# Sparki_Senseboard.net
KiCad netlist of a schematic drawn in EAGLE
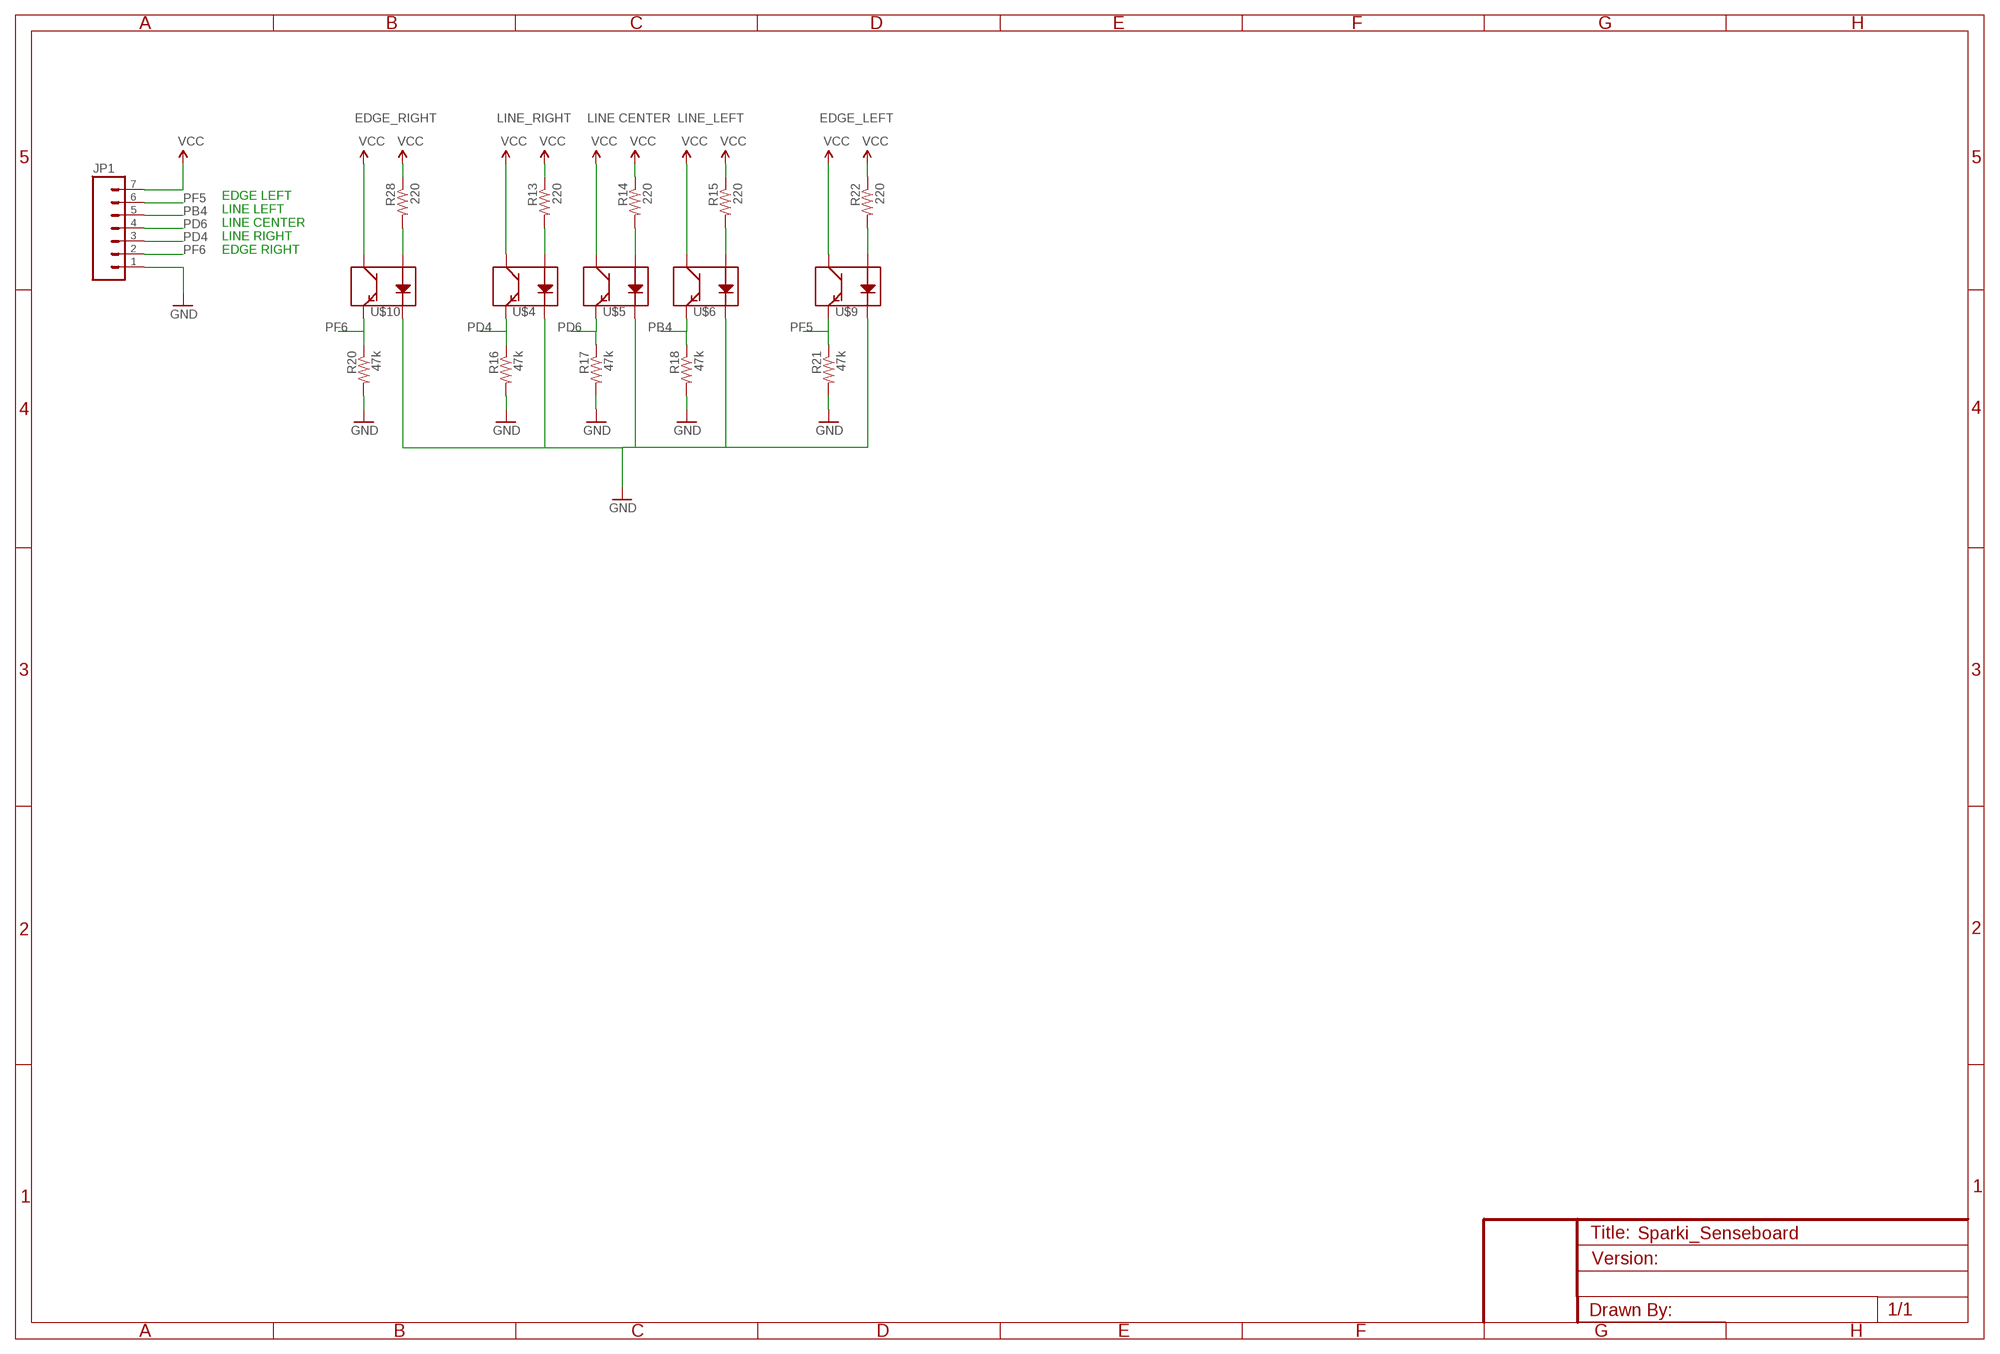
[diagram p0: schematic, sheet 1]

(export (version "E")
  (design (tool "Eeschema 10.0.6"))
  (components
    (comp (ref "JP1")
      (value "M07")
      (footprint "eagle-import:1X07")
      (libsource (lib "eagle-import") (part "M07"))
    )
    (comp (ref "R13")
      (value "220")
      (footprint "eagle-import:0603-RES")
      (libsource (lib "eagle-import") (part "RESISTOR0603-RES"))
    )
    (comp (ref "R14")
      (value "220")
      (footprint "eagle-import:0603-RES")
      (libsource (lib "eagle-import") (part "RESISTOR0603-RES"))
    )
    (comp (ref "R15")
      (value "220")
      (footprint "eagle-import:0603-RES")
      (libsource (lib "eagle-import") (part "RESISTOR0603-RES"))
    )
    (comp (ref "R16")
      (value "47k")
      (footprint "eagle-import:0603-RES")
      (libsource (lib "eagle-import") (part "RESISTOR0603-RES"))
    )
    (comp (ref "R17")
      (value "47k")
      (footprint "eagle-import:0603-RES")
      (libsource (lib "eagle-import") (part "RESISTOR0603-RES"))
    )
    (comp (ref "R18")
      (value "47k")
      (footprint "eagle-import:0603-RES")
      (libsource (lib "eagle-import") (part "RESISTOR0603-RES"))
    )
    (comp (ref "R20")
      (value "47k")
      (footprint "eagle-import:0603-RES")
      (libsource (lib "eagle-import") (part "RESISTOR0603-RES"))
    )
    (comp (ref "R21")
      (value "47k")
      (footprint "eagle-import:0603-RES")
      (libsource (lib "eagle-import") (part "RESISTOR0603-RES"))
    )
    (comp (ref "R22")
      (value "220")
      (footprint "eagle-import:0603-RES")
      (libsource (lib "eagle-import") (part "RESISTOR0603-RES"))
    )
    (comp (ref "R28")
      (value "220")
      (footprint "eagle-import:0603-RES")
      (libsource (lib "eagle-import") (part "RESISTOR0603-RES"))
    )
    (comp (ref "U$4")
      (value "LINE_RIGHT")
      (footprint "eagle-import:QRE1113")
      (libsource (lib "eagle-import") (part "QRE1113"))
    )
    (comp (ref "U$5")
      (value "LINE CENTER")
      (footprint "eagle-import:QRE1113")
      (libsource (lib "eagle-import") (part "QRE1113"))
    )
    (comp (ref "U$6")
      (value "LINE_LEFT")
      (footprint "eagle-import:QRE1113")
      (libsource (lib "eagle-import") (part "QRE1113"))
    )
    (comp (ref "U$9")
      (value "EDGE_LEFT")
      (footprint "eagle-import:QRE1113")
      (libsource (lib "eagle-import") (part "QRE1113"))
    )
    (comp (ref "U$10")
      (value "EDGE_RIGHT")
      (footprint "eagle-import:QRE1113")
      (libsource (lib "eagle-import") (part "QRE1113"))
    )
  )
  (nets
    (net (code "1") (name "/PB4") (class "Default")
      (node (ref "JP1") (pin "5") (pinfunction "5_5") (pintype "passive"))
      (node (ref "R18") (pin "1") (pinfunction "1_1") (pintype "passive"))
      (node (ref "U$6") (pin "4") (pinfunction "E_4") (pintype "bidirectional"))
    )
    (net (code "2") (name "/PD4") (class "Default")
      (node (ref "JP1") (pin "3") (pinfunction "3_3") (pintype "passive"))
      (node (ref "R16") (pin "1") (pinfunction "1_1") (pintype "passive"))
      (node (ref "U$4") (pin "4") (pinfunction "E_4") (pintype "bidirectional"))
    )
    (net (code "3") (name "/PD6") (class "Default")
      (node (ref "JP1") (pin "4") (pinfunction "4_4") (pintype "passive"))
      (node (ref "R17") (pin "1") (pinfunction "1_1") (pintype "passive"))
      (node (ref "U$5") (pin "4") (pinfunction "E_4") (pintype "bidirectional"))
    )
    (net (code "4") (name "/PF5") (class "Default")
      (node (ref "JP1") (pin "6") (pinfunction "6_6") (pintype "passive"))
      (node (ref "R21") (pin "1") (pinfunction "1_1") (pintype "passive"))
      (node (ref "U$9") (pin "4") (pinfunction "E_4") (pintype "bidirectional"))
    )
    (net (code "5") (name "/PF6") (class "Default")
      (node (ref "JP1") (pin "2") (pinfunction "2_2") (pintype "passive"))
      (node (ref "R20") (pin "1") (pinfunction "1_1") (pintype "passive"))
      (node (ref "U$10") (pin "4") (pinfunction "E_4") (pintype "bidirectional"))
    )
    (net (code "6") (name "GND") (class "Default")
      (node (ref "JP1") (pin "1") (pinfunction "1_1") (pintype "passive"))
      (node (ref "R16") (pin "2") (pinfunction "2_2") (pintype "passive"))
      (node (ref "R17") (pin "2") (pinfunction "2_2") (pintype "passive"))
      (node (ref "R18") (pin "2") (pinfunction "2_2") (pintype "passive"))
      (node (ref "R20") (pin "2") (pinfunction "2_2") (pintype "passive"))
      (node (ref "R21") (pin "2") (pinfunction "2_2") (pintype "passive"))
      (node (ref "U$10") (pin "2") (pinfunction "K_2") (pintype "bidirectional"))
      (node (ref "U$4") (pin "2") (pinfunction "K_2") (pintype "bidirectional"))
      (node (ref "U$5") (pin "2") (pinfunction "K_2") (pintype "bidirectional"))
      (node (ref "U$6") (pin "2") (pinfunction "K_2") (pintype "bidirectional"))
      (node (ref "U$9") (pin "2") (pinfunction "K_2") (pintype "bidirectional"))
    )
    (net (code "7") (name "Net-(U$4-A)") (class "Default")
      (node (ref "R13") (pin "2") (pinfunction "2_2") (pintype "passive"))
      (node (ref "U$4") (pin "1") (pinfunction "A_1") (pintype "bidirectional"))
    )
    (net (code "8") (name "Net-(U$5-A)") (class "Default")
      (node (ref "R14") (pin "2") (pinfunction "2_2") (pintype "passive"))
      (node (ref "U$5") (pin "1") (pinfunction "A_1") (pintype "bidirectional"))
    )
    (net (code "9") (name "Net-(U$6-A)") (class "Default")
      (node (ref "R15") (pin "2") (pinfunction "2_2") (pintype "passive"))
      (node (ref "U$6") (pin "1") (pinfunction "A_1") (pintype "bidirectional"))
    )
    (net (code "10") (name "Net-(U$9-A)") (class "Default")
      (node (ref "R22") (pin "2") (pinfunction "2_2") (pintype "passive"))
      (node (ref "U$9") (pin "1") (pinfunction "A_1") (pintype "bidirectional"))
    )
    (net (code "11") (name "Net-(U$10-A)") (class "Default")
      (node (ref "R28") (pin "2") (pinfunction "2_2") (pintype "passive"))
      (node (ref "U$10") (pin "1") (pinfunction "A_1") (pintype "bidirectional"))
    )
    (net (code "12") (name "VCC") (class "Default")
      (node (ref "JP1") (pin "7") (pinfunction "7_7") (pintype "passive"))
      (node (ref "R13") (pin "1") (pinfunction "1_1") (pintype "passive"))
      (node (ref "R14") (pin "1") (pinfunction "1_1") (pintype "passive"))
      (node (ref "R15") (pin "1") (pinfunction "1_1") (pintype "passive"))
      (node (ref "R22") (pin "1") (pinfunction "1_1") (pintype "passive"))
      (node (ref "R28") (pin "1") (pinfunction "1_1") (pintype "passive"))
      (node (ref "U$10") (pin "3") (pinfunction "C_3") (pintype "bidirectional"))
      (node (ref "U$4") (pin "3") (pinfunction "C_3") (pintype "bidirectional"))
      (node (ref "U$5") (pin "3") (pinfunction "C_3") (pintype "bidirectional"))
      (node (ref "U$6") (pin "3") (pinfunction "C_3") (pintype "bidirectional"))
      (node (ref "U$9") (pin "3") (pinfunction "C_3") (pintype "bidirectional"))
    )
  )
)
